# i2c_mux.net
KiCad netlist of a schematic drawn in Altium Designer
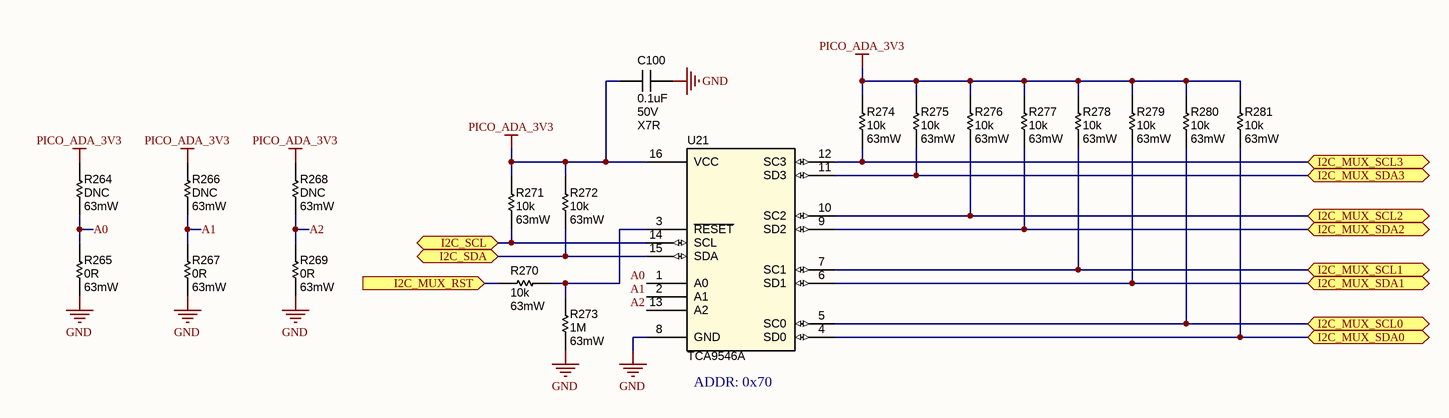
[diagram p0: i2c_mux.SchDoc]

(export (version "E")
  (design (tool "Eeschema 10.0.6"))
  (components
    (comp (ref "C100")
      (value "0.1uF")
      (footprint "CAPC1005X06N")
      (description "CAP CER SMD 0.1UF 50V X7R 0402")
      (fields
        (field (name "TOLERANCE") "10%")
        (field (name "MFR") "Murata Electronics")
        (field (name "VOLTAGE RATING") "50V")
        (field (name "TEMP COEFF") "X7R")
      )
      (libsource (lib "General_Library") (part "CMP-004-0076"))
    )
    (comp (ref "R264")
      (value "DNC")
      (footprint "RESC1005X04N")
      (description "RES SMD 0 OHM JUMPER 1/16W 0402")
      (fields
        (field (name "MFR") "Stackpole Electronics Inc")
        (field (name "TOLERANCE") "Jumper")
        (field (name "WATTAGE") "63mW")
      )
      (libsource (lib "General_Library") (part "CMP-025-0102"))
    )
    (comp (ref "R265")
      (value "0R")
      (footprint "RESC1005X04N")
      (description "RES SMD 0 OHM JUMPER 1/16W 0402")
      (fields
        (field (name "MFR") "Stackpole Electronics Inc")
        (field (name "TOLERANCE") "Jumper")
        (field (name "WATTAGE") "63mW")
      )
      (libsource (lib "General_Library") (part "CMP-025-0102"))
    )
    (comp (ref "R266")
      (value "DNC")
      (footprint "RESC1005X04N")
      (description "RES SMD 0 OHM JUMPER 1/16W 0402")
      (fields
        (field (name "MFR") "Stackpole Electronics Inc")
        (field (name "TOLERANCE") "Jumper")
        (field (name "WATTAGE") "63mW")
      )
      (libsource (lib "General_Library") (part "CMP-025-0102"))
    )
    (comp (ref "R267")
      (value "0R")
      (footprint "RESC1005X04N")
      (description "RES SMD 0 OHM JUMPER 1/16W 0402")
      (fields
        (field (name "MFR") "Stackpole Electronics Inc")
        (field (name "TOLERANCE") "Jumper")
        (field (name "WATTAGE") "63mW")
      )
      (libsource (lib "General_Library") (part "CMP-025-0102"))
    )
    (comp (ref "R268")
      (value "DNC")
      (footprint "RESC1005X04N")
      (description "RES SMD 0 OHM JUMPER 1/16W 0402")
      (fields
        (field (name "MFR") "Stackpole Electronics Inc")
        (field (name "TOLERANCE") "Jumper")
        (field (name "WATTAGE") "63mW")
      )
      (libsource (lib "General_Library") (part "CMP-025-0102"))
    )
    (comp (ref "R269")
      (value "0R")
      (footprint "RESC1005X04N")
      (description "RES SMD 0 OHM JUMPER 1/16W 0402")
      (fields
        (field (name "MFR") "Stackpole Electronics Inc")
        (field (name "TOLERANCE") "Jumper")
        (field (name "WATTAGE") "63mW")
      )
      (libsource (lib "General_Library") (part "CMP-025-0102"))
    )
    (comp (ref "R270")
      (value "10k")
      (footprint "RESC1005X04N")
      (description "RES SMD 10K OHM 0.5% 1/16W 0402")
      (fields
        (field (name "MFR") "Panasonic Electronic Components")
        (field (name "TOLERANCE") "0.5%")
        (field (name "WATTAGE") "63mW")
      )
      (libsource (lib "General_Library") (part "CMP-025-0026"))
    )
    (comp (ref "R271")
      (value "10k")
      (footprint "RESC1005X04N")
      (description "RES SMD 10K OHM 0.5% 1/16W 0402")
      (fields
        (field (name "MFR") "Panasonic Electronic Components")
        (field (name "TOLERANCE") "0.5%")
        (field (name "WATTAGE") "63mW")
      )
      (libsource (lib "General_Library") (part "CMP-025-0026"))
    )
    (comp (ref "R272")
      (value "10k")
      (footprint "RESC1005X04N")
      (description "RES SMD 10K OHM 0.5% 1/16W 0402")
      (fields
        (field (name "MFR") "Panasonic Electronic Components")
        (field (name "TOLERANCE") "0.5%")
        (field (name "WATTAGE") "63mW")
      )
      (libsource (lib "General_Library") (part "CMP-025-0026"))
    )
    (comp (ref "R273")
      (value "1M")
      (footprint "RESC1005X04N")
      (description "RES SMD 1M OHM 1% 1/16W 0402")
      (fields (field (name "TOLERANCE") "1%") (field (name "MFR") "YAGEO") (field (name "WATTAGE") "63mW"))
      (libsource (lib "General_Library") (part "CMP-025-0173"))
    )
    (comp (ref "R274")
      (value "10k")
      (footprint "RESC1005X04N")
      (description "RES SMD 10K OHM 0.5% 1/16W 0402")
      (fields
        (field (name "MFR") "Panasonic Electronic Components")
        (field (name "TOLERANCE") "0.5%")
        (field (name "WATTAGE") "63mW")
      )
      (libsource (lib "General_Library") (part "CMP-025-0026"))
    )
    (comp (ref "R275")
      (value "10k")
      (footprint "RESC1005X04N")
      (description "RES SMD 10K OHM 0.5% 1/16W 0402")
      (fields
        (field (name "MFR") "Panasonic Electronic Components")
        (field (name "TOLERANCE") "0.5%")
        (field (name "WATTAGE") "63mW")
      )
      (libsource (lib "General_Library") (part "CMP-025-0026"))
    )
    (comp (ref "R276")
      (value "10k")
      (footprint "RESC1005X04N")
      (description "RES SMD 10K OHM 0.5% 1/16W 0402")
      (fields
        (field (name "MFR") "Panasonic Electronic Components")
        (field (name "TOLERANCE") "0.5%")
        (field (name "WATTAGE") "63mW")
      )
      (libsource (lib "General_Library") (part "CMP-025-0026"))
    )
    (comp (ref "R277")
      (value "10k")
      (footprint "RESC1005X04N")
      (description "RES SMD 10K OHM 0.5% 1/16W 0402")
      (fields
        (field (name "MFR") "Panasonic Electronic Components")
        (field (name "TOLERANCE") "0.5%")
        (field (name "WATTAGE") "63mW")
      )
      (libsource (lib "General_Library") (part "CMP-025-0026"))
    )
    (comp (ref "R278")
      (value "10k")
      (footprint "RESC1005X04N")
      (description "RES SMD 10K OHM 0.5% 1/16W 0402")
      (fields
        (field (name "MFR") "Panasonic Electronic Components")
        (field (name "TOLERANCE") "0.5%")
        (field (name "WATTAGE") "63mW")
      )
      (libsource (lib "General_Library") (part "CMP-025-0026"))
    )
    (comp (ref "R279")
      (value "10k")
      (footprint "RESC1005X04N")
      (description "RES SMD 10K OHM 0.5% 1/16W 0402")
      (fields
        (field (name "MFR") "Panasonic Electronic Components")
        (field (name "TOLERANCE") "0.5%")
        (field (name "WATTAGE") "63mW")
      )
      (libsource (lib "General_Library") (part "CMP-025-0026"))
    )
    (comp (ref "R280")
      (value "10k")
      (footprint "RESC1005X04N")
      (description "RES SMD 10K OHM 0.5% 1/16W 0402")
      (fields
        (field (name "MFR") "Panasonic Electronic Components")
        (field (name "TOLERANCE") "0.5%")
        (field (name "WATTAGE") "63mW")
      )
      (libsource (lib "General_Library") (part "CMP-025-0026"))
    )
    (comp (ref "R281")
      (value "10k")
      (footprint "RESC1005X04N")
      (description "RES SMD 10K OHM 0.5% 1/16W 0402")
      (fields
        (field (name "MFR") "Panasonic Electronic Components")
        (field (name "TOLERANCE") "0.5%")
        (field (name "WATTAGE") "63mW")
      )
      (libsource (lib "General_Library") (part "CMP-025-0026"))
    )
    (comp (ref "U21")
      (value "TCA9546A")
      (footprint "SOP65P640X120-16N")
      (description "IC BUS SWITCH 2 X 1:4 16TSSOP")
      (fields (field (name "MFR") "Texas Instruments"))
      (libsource (lib "General_Library") (part "CMP-017-0074"))
    )
  )
  (nets
    (net (code "1") (name "/A0") (class "Default")
      (node (ref "R264") (pin "1") (pinfunction "1_1") (pintype "passive"))
      (node (ref "R265") (pin "2") (pinfunction "2_2") (pintype "passive"))
      (node (ref "U21") (pin "1") (pinfunction "A0_1") (pintype "passive"))
    )
    (net (code "2") (name "/A1") (class "Default")
      (node (ref "R266") (pin "1") (pinfunction "1_1") (pintype "passive"))
      (node (ref "R267") (pin "2") (pinfunction "2_2") (pintype "passive"))
      (node (ref "U21") (pin "2") (pinfunction "A1_2") (pintype "passive"))
    )
    (net (code "3") (name "/A2") (class "Default")
      (node (ref "R268") (pin "1") (pinfunction "1_1") (pintype "passive"))
      (node (ref "R269") (pin "2") (pinfunction "2_2") (pintype "passive"))
      (node (ref "U21") (pin "13") (pinfunction "A2_13") (pintype "passive"))
    )
    (net (code "4") (name "/I2C_MUX_RST") (class "Default")
      (node (ref "R270") (pin "1") (pinfunction "1_1") (pintype "passive"))
    )
    (net (code "5") (name "/I2C_MUX_SCL0") (class "Default")
      (node (ref "R280") (pin "1") (pinfunction "1_1") (pintype "passive"))
      (node (ref "U21") (pin "5") (pinfunction "SC0_5") (pintype "bidirectional"))
    )
    (net (code "6") (name "/I2C_MUX_SCL1") (class "Default")
      (node (ref "R278") (pin "1") (pinfunction "1_1") (pintype "passive"))
      (node (ref "U21") (pin "7") (pinfunction "SC1_7") (pintype "bidirectional"))
    )
    (net (code "7") (name "/I2C_MUX_SCL2") (class "Default")
      (node (ref "R276") (pin "1") (pinfunction "1_1") (pintype "passive"))
      (node (ref "U21") (pin "10") (pinfunction "SC2_10") (pintype "bidirectional"))
    )
    (net (code "8") (name "/I2C_MUX_SCL3") (class "Default")
      (node (ref "R274") (pin "1") (pinfunction "1_1") (pintype "passive"))
      (node (ref "U21") (pin "12") (pinfunction "SC3_12") (pintype "bidirectional"))
    )
    (net (code "9") (name "/I2C_MUX_SDA0") (class "Default")
      (node (ref "R281") (pin "1") (pinfunction "1_1") (pintype "passive"))
      (node (ref "U21") (pin "4") (pinfunction "SD0_4") (pintype "bidirectional"))
    )
    (net (code "10") (name "/I2C_MUX_SDA1") (class "Default")
      (node (ref "R279") (pin "1") (pinfunction "1_1") (pintype "passive"))
      (node (ref "U21") (pin "6") (pinfunction "SD1_6") (pintype "bidirectional"))
    )
    (net (code "11") (name "/I2C_MUX_SDA2") (class "Default")
      (node (ref "R277") (pin "1") (pinfunction "1_1") (pintype "passive"))
      (node (ref "U21") (pin "9") (pinfunction "SD2_9") (pintype "bidirectional"))
    )
    (net (code "12") (name "/I2C_MUX_SDA3") (class "Default")
      (node (ref "R275") (pin "1") (pinfunction "1_1") (pintype "passive"))
      (node (ref "U21") (pin "11") (pinfunction "SD3_11") (pintype "bidirectional"))
    )
    (net (code "13") (name "/I2C_SCL") (class "Default")
      (node (ref "R271") (pin "1") (pinfunction "1_1") (pintype "passive"))
      (node (ref "U21") (pin "14") (pinfunction "SCL_14") (pintype "bidirectional"))
    )
    (net (code "14") (name "/I2C_SDA") (class "Default")
      (node (ref "R272") (pin "1") (pinfunction "1_1") (pintype "passive"))
      (node (ref "U21") (pin "15") (pinfunction "SDA_15") (pintype "bidirectional"))
    )
    (net (code "15") (name "GND") (class "Default")
      (node (ref "C100") (pin "1") (pinfunction "1_1") (pintype "passive"))
      (node (ref "R265") (pin "1") (pinfunction "1_1") (pintype "passive"))
      (node (ref "R267") (pin "1") (pinfunction "1_1") (pintype "passive"))
      (node (ref "R269") (pin "1") (pinfunction "1_1") (pintype "passive"))
      (node (ref "R273") (pin "1") (pinfunction "1_1") (pintype "passive"))
      (node (ref "U21") (pin "8") (pinfunction "GND_8") (pintype "power_in"))
    )
    (net (code "16") (name "Net-(U21-~{RESET})") (class "Default")
      (node (ref "R270") (pin "2") (pinfunction "2_2") (pintype "passive"))
      (node (ref "R273") (pin "2") (pinfunction "2_2") (pintype "passive"))
      (node (ref "U21") (pin "3") (pinfunction "~{RESET}_3") (pintype "passive"))
    )
    (net (code "17") (name "PICO_ADA_3V3") (class "Default")
      (node (ref "C100") (pin "2") (pinfunction "2_2") (pintype "passive"))
      (node (ref "R264") (pin "2") (pinfunction "2_2") (pintype "passive"))
      (node (ref "R266") (pin "2") (pinfunction "2_2") (pintype "passive"))
      (node (ref "R268") (pin "2") (pinfunction "2_2") (pintype "passive"))
      (node (ref "R271") (pin "2") (pinfunction "2_2") (pintype "passive"))
      (node (ref "R272") (pin "2") (pinfunction "2_2") (pintype "passive"))
      (node (ref "R274") (pin "2") (pinfunction "2_2") (pintype "passive"))
      (node (ref "R275") (pin "2") (pinfunction "2_2") (pintype "passive"))
      (node (ref "R276") (pin "2") (pinfunction "2_2") (pintype "passive"))
      (node (ref "R277") (pin "2") (pinfunction "2_2") (pintype "passive"))
      (node (ref "R278") (pin "2") (pinfunction "2_2") (pintype "passive"))
      (node (ref "R279") (pin "2") (pinfunction "2_2") (pintype "passive"))
      (node (ref "R280") (pin "2") (pinfunction "2_2") (pintype "passive"))
      (node (ref "R281") (pin "2") (pinfunction "2_2") (pintype "passive"))
      (node (ref "U21") (pin "16") (pinfunction "VCC_16") (pintype "power_in"))
    )
  )
)
